# OBD_Connector.net
KiCad netlist of a schematic drawn in Altium Designer
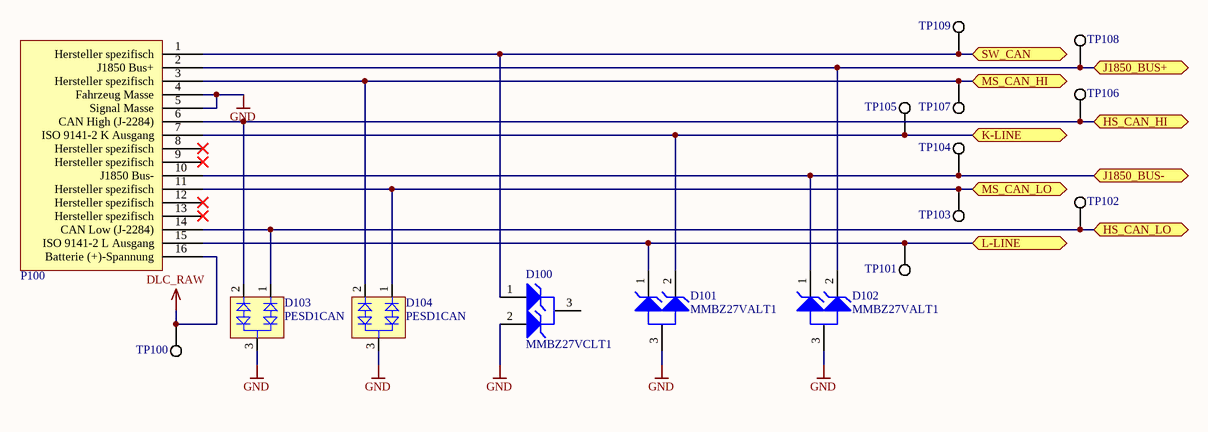
[diagram p0: OBD_Connector.SchDoc]

(export (version "E")
  (design (tool "Eeschema 10.0.6"))
  (components
    (comp (ref "D100")
      (value "MMBZ27VCLT1")
      (footprint "ONSC-SOT-23-3-318-08_V")
      (fields (field (name "MANUFACTURER") "On Semiconductor"))
      (libsource (lib "Altium Content Vault") (part "ONSC-A1A2K3-3"))
    )
    (comp (ref "D101")
      (value "MMBZ27VALT1")
      (footprint "ONSC-SOT-23-3-318-08_V")
      (fields (field (name "MANUFACTURER") "On Semiconductor"))
      (libsource (lib "Altium Content Vault") (part "ONSC-K1K2A3-3"))
    )
    (comp (ref "D102")
      (value "MMBZ27VALT1")
      (footprint "ONSC-SOT-23-3-318-08_V")
      (fields (field (name "MANUFACTURER") "On Semiconductor"))
      (libsource (lib "Altium Content Vault") (part "ONSC-K1K2A3-3"))
    )
    (comp (ref "D103")
      (value "PESD1CAN")
      (footprint "NXP-SOT23-3_V")
      (description "CAN Bus ESD Protection Diode, 200 W, 24 V, -65 to 150 degC, 3-Pin SOT23, RoHS, Tape and Reel")
      (fields (field (name "MANUFACTURER") "NXP Semiconductors"))
      (libsource (lib "Altium Content Vault") (part "NXP-PESD1CAN-SOT23-3"))
    )
    (comp (ref "D104")
      (value "PESD1CAN")
      (footprint "NXP-SOT23-3_V")
      (description "CAN Bus ESD Protection Diode, 200 W, 24 V, -65 to 150 degC, 3-Pin SOT23, RoHS, Tape and Reel")
      (fields (field (name "MANUFACTURER") "NXP Semiconductors"))
      (libsource (lib "Altium Content Vault") (part "NXP-PESD1CAN-SOT23-3"))
    )
    (comp (ref "P100")
      (value "COMTECH ELECTRONIC CO., LTD ,CR-PG032")
      (footprint "a. OBD-Stekcer mit Winkel für Platinenmontage")
      (description "OBD-2 Stiftblock rechtwinklig PCB Montagewinkel")
      (fields
        (field (name "MANUFACTURER") "COMTECH ELECTRONIC CO., LTD")
        (field (name "MANUFACTURER PART NUMBER") "CR-PG032")
      )
      (libsource (lib "NE-SE - Altium Vault Server") (part "OBD-Pinout"))
    )
    (comp (ref "TP100")
      (value "Testpad, 1.0mm x 1.0mm, round")
      (footprint "Testpad, 1.0mm x 1.0mm, round")
      (libsource (lib "NE-SE - Altium Vault Server") (part "Testpoint (No BOM)"))
    )
    (comp (ref "TP101")
      (value "Testpad, 1.0mm x 1.0mm, round")
      (footprint "Testpad, 1.0mm x 1.0mm, round")
      (libsource (lib "NE-SE - Altium Vault Server") (part "Testpoint (No BOM)"))
    )
    (comp (ref "TP102")
      (value "Testpad, 1.0mm x 1.0mm, round")
      (footprint "Testpad, 1.0mm x 1.0mm, round")
      (libsource (lib "NE-SE - Altium Vault Server") (part "Testpoint (No BOM)"))
    )
    (comp (ref "TP103")
      (value "Testpad, 1.0mm x 1.0mm, round")
      (footprint "Testpad, 1.0mm x 1.0mm, round")
      (libsource (lib "NE-SE - Altium Vault Server") (part "Testpoint (No BOM)"))
    )
    (comp (ref "TP104")
      (value "Testpad, 1.0mm x 1.0mm, round")
      (footprint "Testpad, 1.0mm x 1.0mm, round")
      (libsource (lib "NE-SE - Altium Vault Server") (part "Testpoint (No BOM)"))
    )
    (comp (ref "TP105")
      (value "Testpad, 1.0mm x 1.0mm, round")
      (footprint "Testpad, 1.0mm x 1.0mm, round")
      (libsource (lib "NE-SE - Altium Vault Server") (part "Testpoint (No BOM)"))
    )
    (comp (ref "TP106")
      (value "Testpad, 1.0mm x 1.0mm, round")
      (footprint "Testpad, 1.0mm x 1.0mm, round")
      (libsource (lib "NE-SE - Altium Vault Server") (part "Testpoint (No BOM)"))
    )
    (comp (ref "TP107")
      (value "Testpad, 1.0mm x 1.0mm, round")
      (footprint "Testpad, 1.0mm x 1.0mm, round")
      (libsource (lib "NE-SE - Altium Vault Server") (part "Testpoint (No BOM)"))
    )
    (comp (ref "TP108")
      (value "Testpad, 1.0mm x 1.0mm, round")
      (footprint "Testpad, 1.0mm x 1.0mm, round")
      (libsource (lib "NE-SE - Altium Vault Server") (part "Testpoint (No BOM)"))
    )
    (comp (ref "TP109")
      (value "Testpad, 1.0mm x 1.0mm, round")
      (footprint "Testpad, 1.0mm x 1.0mm, round")
      (libsource (lib "NE-SE - Altium Vault Server") (part "Testpoint (No BOM)"))
    )
  )
  (nets
    (net (code "1") (name "/HS_CAN_HI") (class "Default")
      (node (ref "D103") (pin "2") (pinfunction "K2_2") (pintype "passive"))
      (node (ref "P100") (pin "6") (pinfunction "CAN_High_(J-2284)_6") (pintype "passive"))
      (node (ref "TP106") (pin "1") (pinfunction "1_1") (pintype "passive"))
    )
    (net (code "2") (name "/HS_CAN_LO") (class "Default")
      (node (ref "D103") (pin "1") (pinfunction "K1_1") (pintype "passive"))
      (node (ref "P100") (pin "14") (pinfunction "CAN_Low_(J-2284)_14") (pintype "passive"))
      (node (ref "TP102") (pin "1") (pinfunction "1_1") (pintype "passive"))
    )
    (net (code "3") (name "/J1850_BUS+") (class "Default")
      (node (ref "D102") (pin "2") (pinfunction "K2_2") (pintype "passive"))
      (node (ref "P100") (pin "2") (pinfunction "J1850_Bus+_2") (pintype "passive"))
      (node (ref "TP108") (pin "1") (pinfunction "1_1") (pintype "passive"))
    )
    (net (code "4") (name "/J1850_BUS-") (class "Default")
      (node (ref "D102") (pin "1") (pinfunction "K1_1") (pintype "passive"))
      (node (ref "P100") (pin "10") (pinfunction "J1850_Bus-_10") (pintype "passive"))
      (node (ref "TP104") (pin "1") (pinfunction "1_1") (pintype "passive"))
    )
    (net (code "5") (name "/K-LINE") (class "Default")
      (node (ref "D101") (pin "2") (pinfunction "K2_2") (pintype "passive"))
      (node (ref "P100") (pin "7") (pinfunction "ISO_9141-2_K_Ausgang_7") (pintype "passive"))
      (node (ref "TP105") (pin "1") (pinfunction "1_1") (pintype "passive"))
    )
    (net (code "6") (name "/L-LINE") (class "Default")
      (node (ref "D101") (pin "1") (pinfunction "K1_1") (pintype "passive"))
      (node (ref "P100") (pin "15") (pinfunction "ISO_9141-2_L_Ausgang_15") (pintype "passive"))
      (node (ref "TP101") (pin "1") (pinfunction "1_1") (pintype "passive"))
    )
    (net (code "7") (name "/MS_CAN_HI") (class "Default")
      (node (ref "D104") (pin "2") (pinfunction "K2_2") (pintype "passive"))
      (node (ref "P100") (pin "3") (pinfunction "Hersteller_spezifisch_3") (pintype "passive"))
      (node (ref "TP107") (pin "1") (pinfunction "1_1") (pintype "passive"))
    )
    (net (code "8") (name "/MS_CAN_LO") (class "Default")
      (node (ref "D104") (pin "1") (pinfunction "K1_1") (pintype "passive"))
      (node (ref "P100") (pin "11") (pinfunction "Hersteller_spezifisch_11") (pintype "passive"))
      (node (ref "TP103") (pin "1") (pinfunction "1_1") (pintype "passive"))
    )
    (net (code "9") (name "/SW_CAN") (class "Default")
      (node (ref "D100") (pin "1") (pinfunction "A1_1") (pintype "passive"))
      (node (ref "P100") (pin "1") (pinfunction "Hersteller_spezifisch_1") (pintype "passive"))
      (node (ref "TP109") (pin "1") (pinfunction "1_1") (pintype "passive"))
    )
    (net (code "10") (name "DLC_RAW") (class "Default")
      (node (ref "P100") (pin "16") (pinfunction "Batterie_(+)-Spannung_16") (pintype "power_in"))
      (node (ref "TP100") (pin "1") (pinfunction "1_1") (pintype "passive"))
    )
    (net (code "11") (name "GND") (class "Default")
      (node (ref "D100") (pin "2") (pinfunction "A2_2") (pintype "passive"))
      (node (ref "D101") (pin "3") (pinfunction "A_3") (pintype "passive"))
      (node (ref "D102") (pin "3") (pinfunction "A_3") (pintype "passive"))
      (node (ref "D103") (pin "3") (pinfunction "C_3") (pintype "passive"))
      (node (ref "D104") (pin "3") (pinfunction "C_3") (pintype "passive"))
      (node (ref "P100") (pin "4") (pinfunction "Fahrzeug_Masse_4") (pintype "passive"))
      (node (ref "P100") (pin "5") (pinfunction "Signal_Masse_5") (pintype "passive"))
    )
    (net (code "12") (name "unconnected-(D100-K-Pad3)") (class "Default")
      (node (ref "D100") (pin "3") (pinfunction "K_3") (pintype "passive"))
    )
    (net (code "13") (name "unconnected-(P100-Hersteller_spezifisch-Pad8)") (class "Default")
      (node (ref "P100") (pin "8") (pinfunction "Hersteller_spezifisch_8") (pintype "passive+no_connect"))
    )
    (net (code "14") (name "unconnected-(P100-Hersteller_spezifisch-Pad9)") (class "Default")
      (node (ref "P100") (pin "9") (pinfunction "Hersteller_spezifisch_9") (pintype "passive+no_connect"))
    )
    (net (code "15") (name "unconnected-(P100-Hersteller_spezifisch-Pad12)") (class "Default")
      (node (ref "P100") (pin "12") (pinfunction "Hersteller_spezifisch_12") (pintype "passive+no_connect"))
    )
    (net (code "16") (name "unconnected-(P100-Hersteller_spezifisch-Pad13)") (class "Default")
      (node (ref "P100") (pin "13") (pinfunction "Hersteller_spezifisch_13") (pintype "passive+no_connect"))
    )
  )
)
